# LowduinoPTH.net
KiCad netlist of a schematic drawn in EAGLE
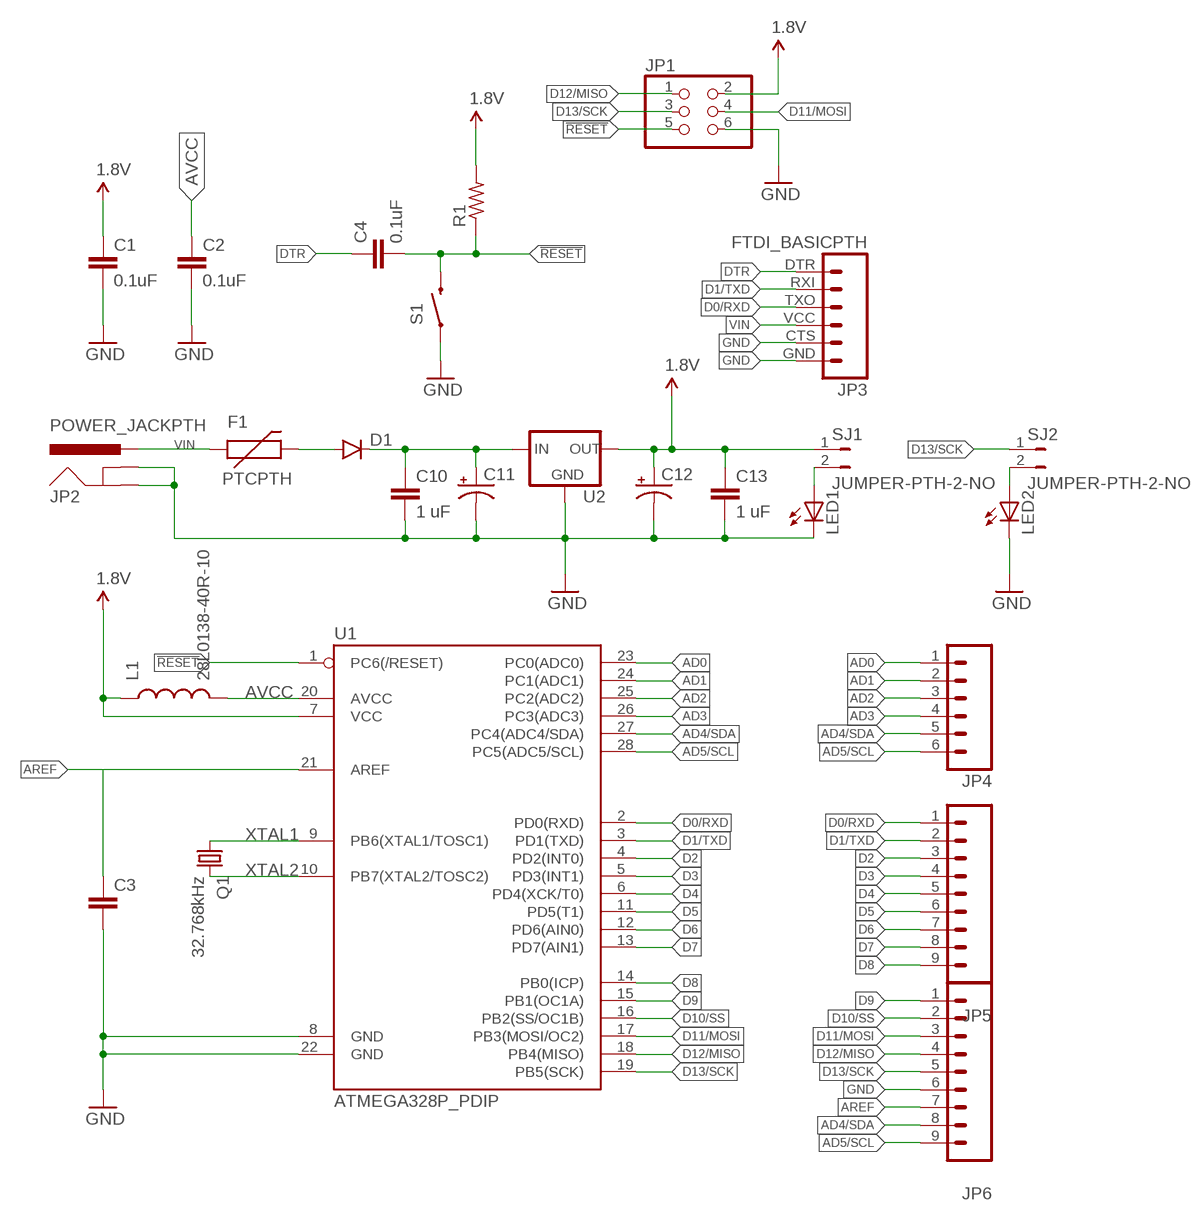
[diagram p0: schematic, sheet 1]

(export (version "E")
  (design (tool "Eeschema 10.0.6"))
  (components
    (comp (ref "C1")
      (value "0.1uF")
      (footprint "eagle-import:CAP-PTH-SMALL2")
      (libsource (lib "eagle-import") (part "CAPPTH2"))
    )
    (comp (ref "C2")
      (value "0.1uF")
      (footprint "eagle-import:CAP-PTH-5MM")
      (libsource (lib "eagle-import") (part "SparkFun-Passives_CAPPTH1"))
    )
    (comp (ref "C3")
      (value "CAPPTH2")
      (footprint "eagle-import:CAP-PTH-SMALL2")
      (libsource (lib "eagle-import") (part "CAPPTH2"))
    )
    (comp (ref "C4")
      (value "0.1uF")
      (footprint "eagle-import:CAP-PTH-LARGE")
      (libsource (lib "eagle-import") (part "SparkFun-Passives_CAPPTH3"))
    )
    (comp (ref "C10")
      (value "1 uF")
      (footprint "eagle-import:CAP-PTH-SMALL2")
      (libsource (lib "eagle-import") (part "CAPPTH2"))
    )
    (comp (ref "C11")
      (value "CPOL-USE2.5-6")
      (footprint "eagle-import:E2,5-6")
      (libsource (lib "eagle-import") (part "CPOL-USE2.5-6"))
    )
    (comp (ref "C12")
      (value "CPOL-USE2.5-6")
      (footprint "eagle-import:E2,5-6")
      (libsource (lib "eagle-import") (part "CPOL-USE2.5-6"))
    )
    (comp (ref "C13")
      (value "1 uF")
      (footprint "eagle-import:CAP-PTH-SMALL2")
      (libsource (lib "eagle-import") (part "CAPPTH2"))
    )
    (comp (ref "D1")
      (value "DIODEPTH")
      (footprint "eagle-import:DIODE-1N4001")
      (libsource (lib "eagle-import") (part "DIODEPTH"))
    )
    (comp (ref "F1")
      (value "PTCPTH")
      (footprint "eagle-import:PTC")
      (libsource (lib "eagle-import") (part "PTCPTH"))
    )
    (comp (ref "JP1")
      (value "PINHD-2X3")
      (footprint "eagle-import:2X03")
      (libsource (lib "eagle-import") (part "PINHD-2X3"))
    )
    (comp (ref "JP2")
      (value "POWER_JACKPTH")
      (footprint "eagle-import:POWER_JACK_PTH")
      (libsource (lib "eagle-import") (part "POWER_JACKPTH"))
    )
    (comp (ref "JP3")
      (value "FTDI_BASICPTH")
      (footprint "eagle-import:FTDI_BASIC")
      (libsource (lib "eagle-import") (part "FTDI_BASICPTH"))
    )
    (comp (ref "JP4")
      (value "M06SILK_FEMALE_PTH")
      (footprint "eagle-import:1X06")
      (libsource (lib "eagle-import") (part "M06SILK_FEMALE_PTH"))
    )
    (comp (ref "JP5")
      (value "M09")
      (footprint "eagle-import:1X09")
      (libsource (lib "eagle-import") (part "M09"))
    )
    (comp (ref "JP6")
      (value "M09")
      (footprint "eagle-import:1X09")
      (libsource (lib "eagle-import") (part "M09"))
    )
    (comp (ref "L1")
      (value "28L0138-40R-10")
      (footprint "eagle-import:AXIAL-0.6")
      (libsource (lib "eagle-import") (part "INDUCTORAXIAL-0.6"))
    )
    (comp (ref "LED1")
      (value "LED3MM")
      (footprint "eagle-import:LED3MM")
      (libsource (lib "eagle-import") (part "LED3MM"))
    )
    (comp (ref "LED2")
      (value "LED3MM")
      (footprint "eagle-import:LED3MM")
      (libsource (lib "eagle-import") (part "LED3MM"))
    )
    (comp (ref "Q1")
      (value "32.768kHz")
      (footprint "eagle-import:TC26H")
      (libsource (lib "eagle-import") (part "CRYSTALTC26H"))
    )
    (comp (ref "R1")
      (value "R-US_0207/10")
      (footprint "eagle-import:0207_10")
      (libsource (lib "eagle-import") (part "R-US_0207/10"))
    )
    (comp (ref "S1")
      (value "SWITCH-MOMENTARY-2PTH")
      (footprint "eagle-import:TACTILE-PTH")
      (libsource (lib "eagle-import") (part "SWITCH-MOMENTARY-2PTH"))
    )
    (comp (ref "SJ1")
      (value "JUMPER-PTH-2-NO")
      (footprint "eagle-import:PTH-JUMPER-2-NO_NO_SILK")
      (libsource (lib "eagle-import") (part "JUMPER-PTH-2-NO"))
    )
    (comp (ref "SJ2")
      (value "JUMPER-PTH-2-NO")
      (footprint "eagle-import:PTH-JUMPER-2-NO_NO_SILK")
      (libsource (lib "eagle-import") (part "JUMPER-PTH-2-NO"))
    )
    (comp (ref "U1")
      (value "ATMEGA328P_PDIP")
      (footprint "eagle-import:DIL28-3")
      (libsource (lib "eagle-import") (part "ATMEGA328P_PDIP"))
    )
    (comp (ref "U2")
      (value "V_REG_78XXTO-92_UNTESTED")
      (footprint "eagle-import:TO-92")
      (libsource (lib "eagle-import") (part "V_REG_78XXTO-92_UNTESTED"))
    )
  )
  (nets
    (net (code "1") (name "/XTAL1") (class "Default")
      (node (ref "Q1") (pin "1") (pinfunction "1_1") (pintype "passive"))
      (node (ref "U1") (pin "9") (pinfunction "PB6(XTAL1/TOSC1)_9") (pintype "bidirectional"))
    )
    (net (code "2") (name "/XTAL2") (class "Default")
      (node (ref "Q1") (pin "2") (pinfunction "2_2") (pintype "passive"))
      (node (ref "U1") (pin "10") (pinfunction "PB7(XTAL2/TOSC2)_10") (pintype "bidirectional"))
    )
    (net (code "3") (name "/~{RESET}") (class "Default")
      (node (ref "C4") (pin "2") (pinfunction "2_2") (pintype "passive"))
      (node (ref "JP1") (pin "5") (pinfunction "5_5") (pintype "passive"))
      (node (ref "R1") (pin "1") (pinfunction "1_1") (pintype "passive"))
      (node (ref "S1") (pin "3") (pinfunction "2_3") (pintype "passive"))
      (node (ref "U1") (pin "1") (pinfunction "PC6(/RESET)_1") (pintype "bidirectional"))
    )
    (net (code "4") (name "1.8V") (class "Default")
      (node (ref "C1") (pin "1") (pinfunction "1_1") (pintype "passive"))
      (node (ref "C12") (pin "+") (pinfunction "+_+") (pintype "passive"))
      (node (ref "C13") (pin "1") (pinfunction "1_1") (pintype "passive"))
      (node (ref "JP1") (pin "2") (pinfunction "2_2") (pintype "passive"))
      (node (ref "L1") (pin "P$1") (pinfunction "1_P$1") (pintype "passive"))
      (node (ref "R1") (pin "2") (pinfunction "2_2") (pintype "passive"))
      (node (ref "SJ1") (pin "1") (pinfunction "1_1") (pintype "passive"))
      (node (ref "U1") (pin "7") (pinfunction "VCC_7") (pintype "bidirectional"))
      (node (ref "U2") (pin "3") (pinfunction "OUT_3") (pintype "output"))
    )
    (net (code "5") (name "AD0") (class "Default")
      (node (ref "JP4") (pin "1") (pinfunction "1_1") (pintype "passive"))
      (node (ref "U1") (pin "23") (pinfunction "PC0(ADC0)_23") (pintype "bidirectional"))
    )
    (net (code "6") (name "AD1") (class "Default")
      (node (ref "JP4") (pin "2") (pinfunction "2_2") (pintype "passive"))
      (node (ref "U1") (pin "24") (pinfunction "PC1(ADC1)_24") (pintype "bidirectional"))
    )
    (net (code "7") (name "AD2") (class "Default")
      (node (ref "JP4") (pin "3") (pinfunction "3_3") (pintype "passive"))
      (node (ref "U1") (pin "25") (pinfunction "PC2(ADC2)_25") (pintype "bidirectional"))
    )
    (net (code "8") (name "AD3") (class "Default")
      (node (ref "JP4") (pin "4") (pinfunction "4_4") (pintype "passive"))
      (node (ref "U1") (pin "26") (pinfunction "PC3(ADC3)_26") (pintype "bidirectional"))
    )
    (net (code "9") (name "AD4{slash}SDA") (class "Default")
      (node (ref "JP4") (pin "5") (pinfunction "5_5") (pintype "passive"))
      (node (ref "JP6") (pin "8") (pinfunction "8_8") (pintype "passive"))
      (node (ref "U1") (pin "27") (pinfunction "PC4(ADC4/SDA)_27") (pintype "bidirectional"))
    )
    (net (code "10") (name "AD5{slash}SCL") (class "Default")
      (node (ref "JP4") (pin "6") (pinfunction "6_6") (pintype "passive"))
      (node (ref "JP6") (pin "9") (pinfunction "9_9") (pintype "passive"))
      (node (ref "U1") (pin "28") (pinfunction "PC5(ADC5/SCL)_28") (pintype "bidirectional"))
    )
    (net (code "11") (name "AREF") (class "Default")
      (node (ref "C3") (pin "1") (pinfunction "1_1") (pintype "passive"))
      (node (ref "JP6") (pin "7") (pinfunction "7_7") (pintype "passive"))
      (node (ref "U1") (pin "21") (pinfunction "AREF_21") (pintype "bidirectional"))
    )
    (net (code "12") (name "AVCC") (class "Default")
      (node (ref "C2") (pin "1") (pinfunction "1_1") (pintype "passive"))
      (node (ref "L1") (pin "P$2") (pinfunction "2_P$2") (pintype "passive"))
      (node (ref "U1") (pin "20") (pinfunction "AVCC_20") (pintype "bidirectional"))
    )
    (net (code "13") (name "D0{slash}RXD") (class "Default")
      (node (ref "JP3") (pin "TXO") (pinfunction "3_TXO") (pintype "passive"))
      (node (ref "JP5") (pin "1") (pinfunction "1_1") (pintype "passive"))
      (node (ref "U1") (pin "2") (pinfunction "PD0(RXD)_2") (pintype "bidirectional"))
    )
    (net (code "14") (name "D1{slash}TXD") (class "Default")
      (node (ref "JP3") (pin "RXI") (pinfunction "2_RXI") (pintype "passive"))
      (node (ref "JP5") (pin "2") (pinfunction "2_2") (pintype "passive"))
      (node (ref "U1") (pin "3") (pinfunction "PD1(TXD)_3") (pintype "bidirectional"))
    )
    (net (code "15") (name "D2") (class "Default")
      (node (ref "JP5") (pin "3") (pinfunction "3_3") (pintype "passive"))
      (node (ref "U1") (pin "4") (pinfunction "PD2(INT0)_4") (pintype "bidirectional"))
    )
    (net (code "16") (name "D3") (class "Default")
      (node (ref "JP5") (pin "4") (pinfunction "4_4") (pintype "passive"))
      (node (ref "U1") (pin "5") (pinfunction "PD3(INT1)_5") (pintype "bidirectional"))
    )
    (net (code "17") (name "D4") (class "Default")
      (node (ref "JP5") (pin "5") (pinfunction "5_5") (pintype "passive"))
      (node (ref "U1") (pin "6") (pinfunction "PD4(XCK/T0)_6") (pintype "bidirectional"))
    )
    (net (code "18") (name "D5") (class "Default")
      (node (ref "JP5") (pin "6") (pinfunction "6_6") (pintype "passive"))
      (node (ref "U1") (pin "11") (pinfunction "PD5(T1)_11") (pintype "bidirectional"))
    )
    (net (code "19") (name "D6") (class "Default")
      (node (ref "JP5") (pin "7") (pinfunction "7_7") (pintype "passive"))
      (node (ref "U1") (pin "12") (pinfunction "PD6(AIN0)_12") (pintype "bidirectional"))
    )
    (net (code "20") (name "D7") (class "Default")
      (node (ref "JP5") (pin "8") (pinfunction "8_8") (pintype "passive"))
      (node (ref "U1") (pin "13") (pinfunction "PD7(AIN1)_13") (pintype "bidirectional"))
    )
    (net (code "21") (name "D8") (class "Default")
      (node (ref "JP5") (pin "9") (pinfunction "9_9") (pintype "passive"))
      (node (ref "U1") (pin "14") (pinfunction "PB0(ICP)_14") (pintype "bidirectional"))
    )
    (net (code "22") (name "D9") (class "Default")
      (node (ref "JP6") (pin "1") (pinfunction "1_1") (pintype "passive"))
      (node (ref "U1") (pin "15") (pinfunction "PB1(OC1A)_15") (pintype "bidirectional"))
    )
    (net (code "23") (name "D10{slash}SS") (class "Default")
      (node (ref "JP6") (pin "2") (pinfunction "2_2") (pintype "passive"))
      (node (ref "U1") (pin "16") (pinfunction "PB2(SS/OC1B)_16") (pintype "bidirectional"))
    )
    (net (code "24") (name "D11{slash}MOSI") (class "Default")
      (node (ref "JP1") (pin "4") (pinfunction "4_4") (pintype "passive"))
      (node (ref "JP6") (pin "3") (pinfunction "3_3") (pintype "passive"))
      (node (ref "U1") (pin "17") (pinfunction "PB3(MOSI/OC2)_17") (pintype "bidirectional"))
    )
    (net (code "25") (name "D12{slash}MISO") (class "Default")
      (node (ref "JP1") (pin "1") (pinfunction "1_1") (pintype "passive"))
      (node (ref "JP6") (pin "4") (pinfunction "4_4") (pintype "passive"))
      (node (ref "U1") (pin "18") (pinfunction "PB4(MISO)_18") (pintype "bidirectional"))
    )
    (net (code "26") (name "D13{slash}SCK") (class "Default")
      (node (ref "JP1") (pin "3") (pinfunction "3_3") (pintype "passive"))
      (node (ref "JP6") (pin "5") (pinfunction "5_5") (pintype "passive"))
      (node (ref "SJ2") (pin "1") (pinfunction "1_1") (pintype "passive"))
      (node (ref "U1") (pin "19") (pinfunction "PB5(SCK)_19") (pintype "bidirectional"))
    )
    (net (code "27") (name "DTR") (class "Default")
      (node (ref "C4") (pin "1") (pinfunction "1_1") (pintype "passive"))
      (node (ref "JP3") (pin "DTR") (pinfunction "1_DTR") (pintype "passive"))
    )
    (net (code "28") (name "GND") (class "Default")
      (node (ref "C1") (pin "2") (pinfunction "2_2") (pintype "passive"))
      (node (ref "C10") (pin "2") (pinfunction "2_2") (pintype "passive"))
      (node (ref "C11") (pin "-") (pinfunction "-_-") (pintype "passive"))
      (node (ref "C12") (pin "-") (pinfunction "-_-") (pintype "passive"))
      (node (ref "C13") (pin "2") (pinfunction "2_2") (pintype "passive"))
      (node (ref "C2") (pin "2") (pinfunction "2_2") (pintype "passive"))
      (node (ref "C3") (pin "2") (pinfunction "2_2") (pintype "passive"))
      (node (ref "JP1") (pin "6") (pinfunction "6_6") (pintype "passive"))
      (node (ref "JP2") (pin "GND") (pinfunction "GND_GND") (pintype "bidirectional"))
      (node (ref "JP2") (pin "GNDBREAK") (pinfunction "GNDBREAK_GNDBREAK") (pintype "bidirectional"))
      (node (ref "JP3") (pin "CTS") (pinfunction "5_CTS") (pintype "passive"))
      (node (ref "JP3") (pin "GND") (pinfunction "6_GND") (pintype "passive"))
      (node (ref "JP6") (pin "6") (pinfunction "6_6") (pintype "passive"))
      (node (ref "LED1") (pin "K") (pinfunction "C_K") (pintype "passive"))
      (node (ref "LED2") (pin "K") (pinfunction "C_K") (pintype "passive"))
      (node (ref "S1") (pin "1") (pinfunction "1_1") (pintype "passive"))
      (node (ref "U1") (pin "22") (pinfunction "GND_22") (pintype "bidirectional"))
      (node (ref "U1") (pin "8") (pinfunction "GND_8") (pintype "bidirectional"))
      (node (ref "U2") (pin "1") (pinfunction "GND_1") (pintype "input"))
    )
    (net (code "29") (name "Net-(F1-2)") (class "Default")
      (node (ref "D1") (pin "A") (pinfunction "A_A") (pintype "passive"))
      (node (ref "F1") (pin "P$2") (pinfunction "2_P$2") (pintype "bidirectional"))
    )
    (net (code "30") (name "Net-(LED1-PadA)") (class "Default")
      (node (ref "LED1") (pin "A") (pinfunction "A_A") (pintype "passive"))
      (node (ref "SJ1") (pin "2") (pinfunction "2_2") (pintype "passive"))
    )
    (net (code "31") (name "Net-(LED2-PadA)") (class "Default")
      (node (ref "LED2") (pin "A") (pinfunction "A_A") (pintype "passive"))
      (node (ref "SJ2") (pin "2") (pinfunction "2_2") (pintype "passive"))
    )
    (net (code "32") (name "Net-(U2-IN)") (class "Default")
      (node (ref "C10") (pin "1") (pinfunction "1_1") (pintype "passive"))
      (node (ref "C11") (pin "+") (pinfunction "+_+") (pintype "passive"))
      (node (ref "D1") (pin "C") (pinfunction "C_C") (pintype "passive"))
      (node (ref "U2") (pin "2") (pinfunction "IN_2") (pintype "input"))
    )
    (net (code "33") (name "VIN") (class "Default")
      (node (ref "F1") (pin "P$1") (pinfunction "1_P$1") (pintype "bidirectional"))
      (node (ref "JP2") (pin "PWR") (pinfunction "PWR_PWR") (pintype "bidirectional"))
      (node (ref "JP3") (pin "VCC") (pinfunction "4_VCC") (pintype "passive"))
    )
  )
)
